# NEW_10.net
KiCad netlist of a schematic drawn in EAGLE
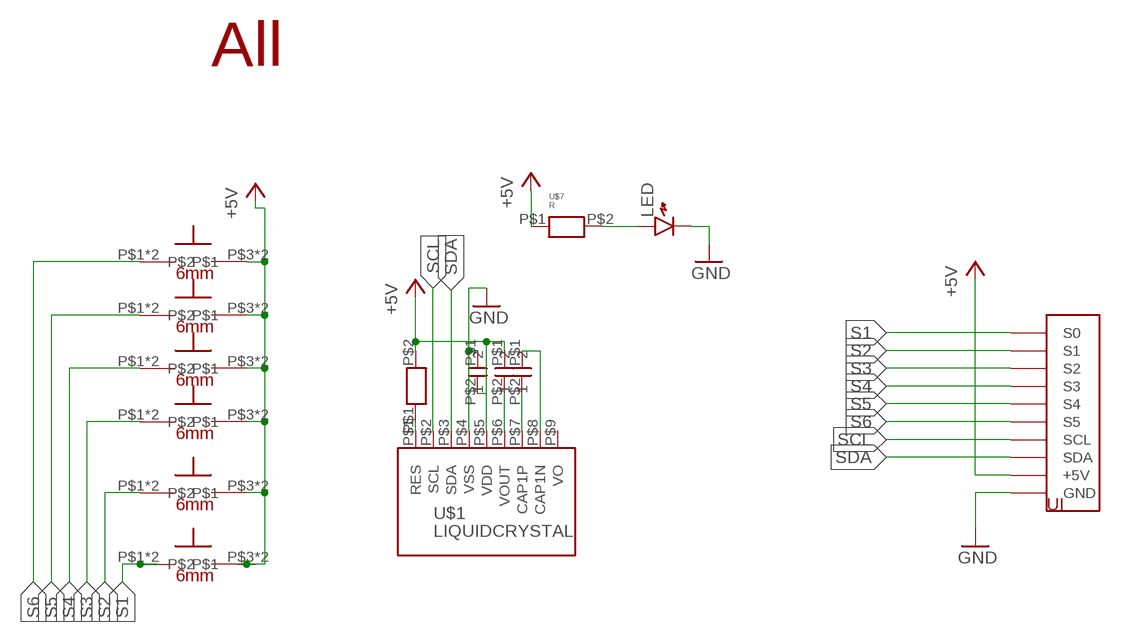
[diagram p0: schematic, sheet 1]

(export (version "E")
  (design (tool "Eeschema 10.0.6"))
  (components
    (comp (ref "LED")
      (value "LED1608")
      (footprint "eagle-import:LED1608")
      (libsource (lib "eagle-import") (part "LED1608"))
    )
    (comp (ref "U$1")
      (value "LIQUIDCRYSTAL")
      (footprint "eagle-import:LIQUIDCRYSTAL")
      (libsource (lib "eagle-import") (part "LIQUIDCRYSTAL"))
    )
    (comp (ref "U$2")
      (value "1608")
      (footprint "eagle-import:CON")
      (libsource (lib "eagle-import") (part "1608"))
    )
    (comp (ref "U$3")
      (value "1608")
      (footprint "eagle-import:CON")
      (libsource (lib "eagle-import") (part "1608"))
    )
    (comp (ref "U$4") (value "R") (footprint "eagle-import:1608") (libsource (lib "eagle-import") (part "R")))
    (comp (ref "U$5")
      (value "1608")
      (footprint "eagle-import:CON")
      (libsource (lib "eagle-import") (part "1608"))
    )
    (comp (ref "U$6")
      (value "TAKUTO6MM")
      (footprint "eagle-import:TAKUTO6MM")
      (libsource (lib "eagle-import") (part "TAKUTO6MM"))
    )
    (comp (ref "U$7") (value "R") (footprint "eagle-import:1608") (libsource (lib "eagle-import") (part "R")))
    (comp (ref "U$8") (value "UI") (footprint "eagle-import:UI") (libsource (lib "eagle-import") (part "UI")))
    (comp (ref "U$9")
      (value "ALL")
      (footprint "eagle-import:ALL")
      (libsource (lib "eagle-import") (part "ALL"))
    )
    (comp (ref "U$10")
      (value "TAKUTO6MM")
      (footprint "eagle-import:TAKUTO6MM")
      (libsource (lib "eagle-import") (part "TAKUTO6MM"))
    )
    (comp (ref "U$11")
      (value "TAKUTO6MM")
      (footprint "eagle-import:TAKUTO6MM")
      (libsource (lib "eagle-import") (part "TAKUTO6MM"))
    )
    (comp (ref "U$12")
      (value "TAKUTO6MM")
      (footprint "eagle-import:TAKUTO6MM")
      (libsource (lib "eagle-import") (part "TAKUTO6MM"))
    )
    (comp (ref "U$13")
      (value "TAKUTO6MM")
      (footprint "eagle-import:TAKUTO6MM")
      (libsource (lib "eagle-import") (part "TAKUTO6MM"))
    )
    (comp (ref "U$14")
      (value "TAKUTO6MM")
      (footprint "eagle-import:TAKUTO6MM")
      (libsource (lib "eagle-import") (part "TAKUTO6MM"))
    )
  )
  (nets
    (net (code "1") (name "+5V") (class "Default")
      (node (ref "U$1") (pin "P$5") (pinfunction "VDD_P$5") (pintype "bidirectional"))
      (node (ref "U$10") (pin "P$3") (pinfunction "P$2_P$3") (pintype "bidirectional"))
      (node (ref "U$10") (pin "P$4") (pinfunction "P$2_P$4") (pintype "bidirectional"))
      (node (ref "U$11") (pin "P$3") (pinfunction "P$2_P$3") (pintype "bidirectional"))
      (node (ref "U$11") (pin "P$4") (pinfunction "P$2_P$4") (pintype "bidirectional"))
      (node (ref "U$12") (pin "P$3") (pinfunction "P$2_P$3") (pintype "bidirectional"))
      (node (ref "U$12") (pin "P$4") (pinfunction "P$2_P$4") (pintype "bidirectional"))
      (node (ref "U$13") (pin "P$3") (pinfunction "P$2_P$3") (pintype "bidirectional"))
      (node (ref "U$13") (pin "P$4") (pinfunction "P$2_P$4") (pintype "bidirectional"))
      (node (ref "U$14") (pin "P$3") (pinfunction "P$2_P$3") (pintype "bidirectional"))
      (node (ref "U$14") (pin "P$4") (pinfunction "P$2_P$4") (pintype "bidirectional"))
      (node (ref "U$2") (pin "P$1") (pinfunction "1_P$1") (pintype "bidirectional"))
      (node (ref "U$4") (pin "P$2") (pinfunction "P$2_P$2") (pintype "bidirectional"))
      (node (ref "U$5") (pin "P$2") (pinfunction "2_P$2") (pintype "bidirectional"))
      (node (ref "U$6") (pin "P$3") (pinfunction "P$2_P$3") (pintype "bidirectional"))
      (node (ref "U$6") (pin "P$4") (pinfunction "P$2_P$4") (pintype "bidirectional"))
      (node (ref "U$7") (pin "P$1") (pinfunction "P$1_P$1") (pintype "bidirectional"))
      (node (ref "U$8") (pin "P$1") (pinfunction "+5V_P$1") (pintype "bidirectional"))
    )
    (net (code "2") (name "GND") (class "Default")
      (node (ref "LED") (pin "K") (pinfunction "K_K") (pintype "passive"))
      (node (ref "U$1") (pin "P$4") (pinfunction "VSS_P$4") (pintype "bidirectional"))
      (node (ref "U$5") (pin "P$1") (pinfunction "1_P$1") (pintype "bidirectional"))
      (node (ref "U$8") (pin "P$2") (pinfunction "GND_P$2") (pintype "bidirectional"))
    )
    (net (code "3") (name "Net-(LED-PadA)") (class "Default")
      (node (ref "LED") (pin "A") (pinfunction "A_A") (pintype "passive"))
      (node (ref "U$7") (pin "P$2") (pinfunction "P$2_P$2") (pintype "bidirectional"))
    )
    (net (code "4") (name "Net-(U$1-CAP1N)") (class "Default")
      (node (ref "U$1") (pin "P$8") (pinfunction "CAP1N_P$8") (pintype "bidirectional"))
      (node (ref "U$3") (pin "P$1") (pinfunction "1_P$1") (pintype "bidirectional"))
    )
    (net (code "5") (name "Net-(U$1-CAP1P)") (class "Default")
      (node (ref "U$1") (pin "P$7") (pinfunction "CAP1P_P$7") (pintype "bidirectional"))
      (node (ref "U$3") (pin "P$2") (pinfunction "2_P$2") (pintype "bidirectional"))
    )
    (net (code "6") (name "Net-(U$1-RES)") (class "Default")
      (node (ref "U$1") (pin "P$1") (pinfunction "RES_P$1") (pintype "bidirectional"))
      (node (ref "U$4") (pin "P$1") (pinfunction "P$1_P$1") (pintype "bidirectional"))
    )
    (net (code "7") (name "Net-(U$1-VOUT)") (class "Default")
      (node (ref "U$1") (pin "P$6") (pinfunction "VOUT_P$6") (pintype "bidirectional"))
      (node (ref "U$2") (pin "P$2") (pinfunction "2_P$2") (pintype "bidirectional"))
    )
    (net (code "8") (name "S1") (class "Default")
      (node (ref "U$6") (pin "P$1") (pinfunction "P$1_P$1") (pintype "bidirectional"))
      (node (ref "U$6") (pin "P$2") (pinfunction "P$1_P$2") (pintype "bidirectional"))
      (node (ref "U$8") (pin "P$3") (pinfunction "S0_P$3") (pintype "bidirectional"))
    )
    (net (code "9") (name "S2") (class "Default")
      (node (ref "U$10") (pin "P$1") (pinfunction "P$1_P$1") (pintype "bidirectional"))
      (node (ref "U$10") (pin "P$2") (pinfunction "P$1_P$2") (pintype "bidirectional"))
      (node (ref "U$8") (pin "P$4") (pinfunction "S1_P$4") (pintype "bidirectional"))
    )
    (net (code "10") (name "S3") (class "Default")
      (node (ref "U$11") (pin "P$1") (pinfunction "P$1_P$1") (pintype "bidirectional"))
      (node (ref "U$11") (pin "P$2") (pinfunction "P$1_P$2") (pintype "bidirectional"))
      (node (ref "U$8") (pin "P$5") (pinfunction "S2_P$5") (pintype "bidirectional"))
    )
    (net (code "11") (name "S4") (class "Default")
      (node (ref "U$12") (pin "P$1") (pinfunction "P$1_P$1") (pintype "bidirectional"))
      (node (ref "U$12") (pin "P$2") (pinfunction "P$1_P$2") (pintype "bidirectional"))
      (node (ref "U$8") (pin "P$6") (pinfunction "S3_P$6") (pintype "bidirectional"))
    )
    (net (code "12") (name "S5") (class "Default")
      (node (ref "U$13") (pin "P$1") (pinfunction "P$1_P$1") (pintype "bidirectional"))
      (node (ref "U$13") (pin "P$2") (pinfunction "P$1_P$2") (pintype "bidirectional"))
      (node (ref "U$8") (pin "P$7") (pinfunction "S4_P$7") (pintype "bidirectional"))
    )
    (net (code "13") (name "S6") (class "Default")
      (node (ref "U$14") (pin "P$1") (pinfunction "P$1_P$1") (pintype "bidirectional"))
      (node (ref "U$14") (pin "P$2") (pinfunction "P$1_P$2") (pintype "bidirectional"))
      (node (ref "U$8") (pin "P$8") (pinfunction "S5_P$8") (pintype "bidirectional"))
    )
    (net (code "14") (name "SCL") (class "Default")
      (node (ref "U$1") (pin "P$2") (pinfunction "SCL_P$2") (pintype "bidirectional"))
      (node (ref "U$8") (pin "P$9") (pinfunction "SCL_P$9") (pintype "bidirectional"))
    )
    (net (code "15") (name "SDA") (class "Default")
      (node (ref "U$1") (pin "P$3") (pinfunction "SDA_P$3") (pintype "bidirectional"))
      (node (ref "U$8") (pin "P$10") (pinfunction "SDA_P$10") (pintype "bidirectional"))
    )
    (net (code "16") (name "unconnected-(U$1-VO-PadP$9)") (class "Default")
      (node (ref "U$1") (pin "P$9") (pinfunction "VO_P$9") (pintype "bidirectional"))
    )
  )
)
